# 3x3Bottom.net
KiCad netlist of a schematic drawn in EAGLE
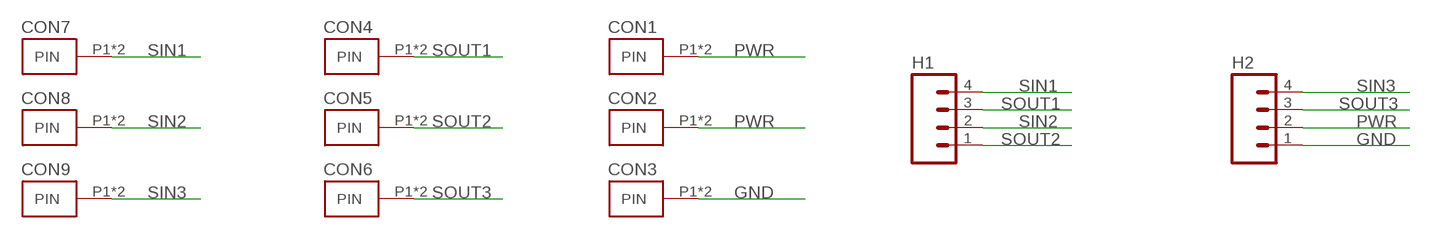
[diagram p0: schematic, sheet 1]

(export (version "E")
  (design (tool "Eeschema 10.0.6"))
  (components
    (comp (ref "CON1")
      (value "SHIELD_FINGER0820")
      (footprint "eagle-import:SHIELD_FINGER_PKG")
      (libsource (lib "eagle-import") (part "SHIELD_FINGER0820"))
    )
    (comp (ref "CON2")
      (value "SHIELD_FINGER0820")
      (footprint "eagle-import:SHIELD_FINGER_PKG")
      (libsource (lib "eagle-import") (part "SHIELD_FINGER0820"))
    )
    (comp (ref "CON3")
      (value "SHIELD_FINGER0820")
      (footprint "eagle-import:SHIELD_FINGER_PKG")
      (libsource (lib "eagle-import") (part "SHIELD_FINGER0820"))
    )
    (comp (ref "CON4")
      (value "SHIELD_FINGER0820")
      (footprint "eagle-import:SHIELD_FINGER_PKG")
      (libsource (lib "eagle-import") (part "SHIELD_FINGER0820"))
    )
    (comp (ref "CON5")
      (value "SHIELD_FINGER0820")
      (footprint "eagle-import:SHIELD_FINGER_PKG")
      (libsource (lib "eagle-import") (part "SHIELD_FINGER0820"))
    )
    (comp (ref "CON6")
      (value "SHIELD_FINGER0820")
      (footprint "eagle-import:SHIELD_FINGER_PKG")
      (libsource (lib "eagle-import") (part "SHIELD_FINGER0820"))
    )
    (comp (ref "CON7")
      (value "SHIELD_FINGER0820")
      (footprint "eagle-import:SHIELD_FINGER_PKG")
      (libsource (lib "eagle-import") (part "SHIELD_FINGER0820"))
    )
    (comp (ref "CON8")
      (value "SHIELD_FINGER0820")
      (footprint "eagle-import:SHIELD_FINGER_PKG")
      (libsource (lib "eagle-import") (part "SHIELD_FINGER0820"))
    )
    (comp (ref "CON9")
      (value "SHIELD_FINGER0820")
      (footprint "eagle-import:SHIELD_FINGER_PKG")
      (libsource (lib "eagle-import") (part "SHIELD_FINGER0820"))
    )
    (comp (ref "H1")
      (value "M04")
      (footprint "eagle-import:1X04_NO_HOLES")
      (libsource (lib "eagle-import") (part "M04"))
    )
    (comp (ref "H2")
      (value "M04")
      (footprint "eagle-import:1X04_NO_HOLES")
      (libsource (lib "eagle-import") (part "M04"))
    )
  )
  (nets
    (net (code "1") (name "/GND") (class "Default")
      (node (ref "CON3") (pin "P1") (pinfunction "PIN_P1") (pintype "bidirectional"))
      (node (ref "CON3") (pin "P2") (pinfunction "PIN_P2") (pintype "bidirectional"))
      (node (ref "H2") (pin "1") (pinfunction "1_1") (pintype "passive"))
    )
    (net (code "2") (name "/PWR") (class "Default")
      (node (ref "CON1") (pin "P1") (pinfunction "PIN_P1") (pintype "bidirectional"))
      (node (ref "CON1") (pin "P2") (pinfunction "PIN_P2") (pintype "bidirectional"))
      (node (ref "CON2") (pin "P1") (pinfunction "PIN_P1") (pintype "bidirectional"))
      (node (ref "CON2") (pin "P2") (pinfunction "PIN_P2") (pintype "bidirectional"))
      (node (ref "H2") (pin "2") (pinfunction "2_2") (pintype "passive"))
    )
    (net (code "3") (name "/SIN1") (class "Default")
      (node (ref "CON7") (pin "P1") (pinfunction "PIN_P1") (pintype "bidirectional"))
      (node (ref "CON7") (pin "P2") (pinfunction "PIN_P2") (pintype "bidirectional"))
      (node (ref "H1") (pin "4") (pinfunction "4_4") (pintype "passive"))
    )
    (net (code "4") (name "/SIN2") (class "Default")
      (node (ref "CON8") (pin "P1") (pinfunction "PIN_P1") (pintype "bidirectional"))
      (node (ref "CON8") (pin "P2") (pinfunction "PIN_P2") (pintype "bidirectional"))
      (node (ref "H1") (pin "2") (pinfunction "2_2") (pintype "passive"))
    )
    (net (code "5") (name "/SIN3") (class "Default")
      (node (ref "CON9") (pin "P1") (pinfunction "PIN_P1") (pintype "bidirectional"))
      (node (ref "CON9") (pin "P2") (pinfunction "PIN_P2") (pintype "bidirectional"))
      (node (ref "H2") (pin "4") (pinfunction "4_4") (pintype "passive"))
    )
    (net (code "6") (name "/SOUT1") (class "Default")
      (node (ref "CON4") (pin "P1") (pinfunction "PIN_P1") (pintype "bidirectional"))
      (node (ref "CON4") (pin "P2") (pinfunction "PIN_P2") (pintype "bidirectional"))
      (node (ref "H1") (pin "3") (pinfunction "3_3") (pintype "passive"))
    )
    (net (code "7") (name "/SOUT2") (class "Default")
      (node (ref "CON5") (pin "P1") (pinfunction "PIN_P1") (pintype "bidirectional"))
      (node (ref "CON5") (pin "P2") (pinfunction "PIN_P2") (pintype "bidirectional"))
      (node (ref "H1") (pin "1") (pinfunction "1_1") (pintype "passive"))
    )
    (net (code "8") (name "/SOUT3") (class "Default")
      (node (ref "CON6") (pin "P1") (pinfunction "PIN_P1") (pintype "bidirectional"))
      (node (ref "CON6") (pin "P2") (pinfunction "PIN_P2") (pintype "bidirectional"))
      (node (ref "H2") (pin "3") (pinfunction "3_3") (pintype "passive"))
    )
  )
)
